# 1_power.net
KiCad netlist of a schematic drawn in Altium Designer
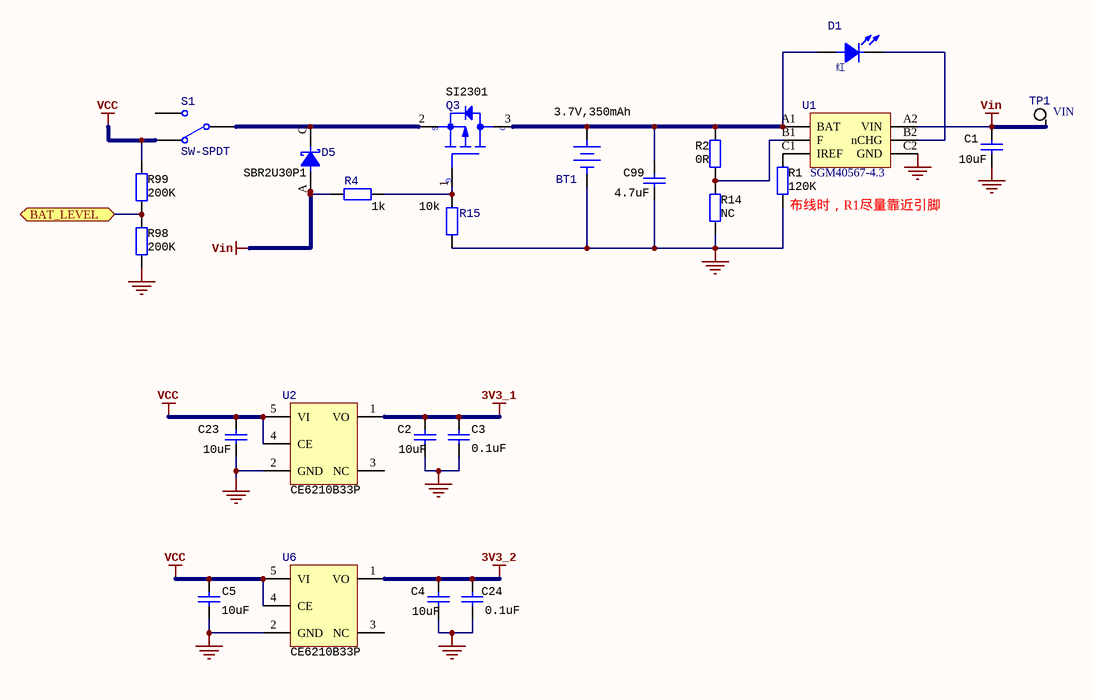
[diagram p0: 1.power.SchDoc]

(export (version "E")
  (design (tool "Eeschema 10.0.6"))
  (components
    (comp (ref "BT1")
      (value "3.7V,350mAh")
      (footprint "2P/1.0MM立式贴片座子")
      (description "4.2V Li-lon")
      (fields (field (name "MANUFACTURER") "?"))
      (libsource (lib "03.常用器件") (part "Battery"))
    )
    (comp (ref "C1")
      (value "10uF")
      (footprint "C0603")
      (description "CAP, CERM, 0.01uF, 100V, +/-5%, X7R, 0603")
      (fields (field (name "PARTNUMBER") "06031C103JAT2A") (field (name "MANUFACTURER") "AVX"))
      (libsource (lib "03.常用器件") (part "CAP1_npol"))
    )
    (comp (ref "C2")
      (value "10uF")
      (footprint "0603")
      (description "CAP, CERM, 0.01uF, 100V, +/-5%, X7R, 0603")
      (fields (field (name "PARTNUMBER") "06031C103JAT2A") (field (name "MANUFACTURER") "AVX"))
      (libsource (lib "03.常用器件") (part "CAP1_npol"))
    )
    (comp (ref "C3")
      (value "0.1uF")
      (footprint "0402")
      (description "CAP, CERM, 0.01uF, 100V, +/-5%, X7R, 0603")
      (fields (field (name "PARTNUMBER") "06031C103JAT2A") (field (name "MANUFACTURER") "AVX"))
      (libsource (lib "03.常用器件") (part "CAP1_npol"))
    )
    (comp (ref "C4")
      (value "10uF")
      (footprint "0603")
      (description "CAP, CERM, 0.01uF, 100V, +/-5%, X7R, 0603")
      (fields (field (name "PARTNUMBER") "06031C103JAT2A") (field (name "MANUFACTURER") "AVX"))
      (libsource (lib "03.常用器件") (part "CAP1_npol"))
    )
    (comp (ref "C5")
      (value "10uF")
      (footprint "0603")
      (description "CAP, CERM, 0.01uF, 100V, +/-5%, X7R, 0603")
      (fields (field (name "PARTNUMBER") "06031C103JAT2A") (field (name "MANUFACTURER") "AVX"))
      (libsource (lib "03.常用器件") (part "CAP1_npol"))
    )
    (comp (ref "C23")
      (value "10uF")
      (footprint "0603")
      (description "CAP, CERM, 0.01uF, 100V, +/-5%, X7R, 0603")
      (fields (field (name "PARTNUMBER") "06031C103JAT2A") (field (name "MANUFACTURER") "AVX"))
      (libsource (lib "03.常用器件") (part "CAP1_npol"))
    )
    (comp (ref "C24")
      (value "0.1uF")
      (footprint "0402")
      (description "CAP, CERM, 0.01uF, 100V, +/-5%, X7R, 0603")
      (fields (field (name "PARTNUMBER") "06031C103JAT2A") (field (name "MANUFACTURER") "AVX"))
      (libsource (lib "03.常用器件") (part "CAP1_npol"))
    )
    (comp (ref "C99")
      (value "4.7uF")
      (footprint "C0603")
      (description "CAP, CERM, 0.01uF, 100V, +/-5%, X7R, 0603")
      (fields (field (name "PARTNUMBER") "06031C103JAT2A") (field (name "MANUFACTURER") "AVX"))
      (libsource (lib "03.常用器件") (part "CAP1_npol"))
    )
    (comp (ref "D1")
      (value "红")
      (footprint "0603LED")
      (fields (field (name "MANUFACTURER") "?"))
      (libsource (lib "03.常用器件") (part "LED1"))
    )
    (comp (ref "D5")
      (value "SBR2U30P1")
      (footprint "POWERDI123")
      (fields (field (name "PARTNUMBER") "?") (field (name "PUBLISHER") "Altium Limited"))
      (libsource (lib "03.常用器件") (part "Diode_Schottky"))
    )
    (comp (ref "Q3")
      (value "SI2301")
      (footprint "SOT23-3")
      (fields (field (name "MANUFACTURER") "?"))
      (libsource (lib "03.常用器件") (part "PMOS"))
    )
    (comp (ref "R1")
      (value "120K")
      (footprint "R0402")
      (description "RES, 1.0k ohm, 5%, 0.1W, 0603")
      (fields
        (field (name "PARTNUMBER") "RC0603JR-071KL")
        (field (name "MANUFACTURER") "Yageo America")
        (field (name "PUBLISHER") "Texas Instruments")
      )
      (libsource (lib "") (part "RES1_1"))
    )
    (comp (ref "R2")
      (value "0R")
      (footprint "R0402")
      (description "RES, 1.0k ohm, 5%, 0.1W, 0603")
      (fields
        (field (name "PARTNUMBER") "RC0603JR-071KL")
        (field (name "MANUFACTURER") "Yageo America")
        (field (name "PUBLISHER") "Texas Instruments")
      )
      (libsource (lib "03.常用器件") (part "RES1"))
    )
    (comp (ref "R4")
      (value "1k")
      (footprint "R0402")
      (description "Resistor")
      (fields (field (name "PUBLISHER") "Altium Limited"))
      (libsource (lib "") (part "Res2_1"))
    )
    (comp (ref "R14")
      (value "NC")
      (footprint "R0402")
      (description "RES, 1.0k ohm, 5%, 0.1W, 0603")
      (fields
        (field (name "PARTNUMBER") "RC0603JR-071KL")
        (field (name "MANUFACTURER") "Yageo America")
        (field (name "PUBLISHER") "Texas Instruments")
      )
      (libsource (lib "03.常用器件") (part "RES1"))
    )
    (comp (ref "R15")
      (value "10k")
      (footprint "R0402")
      (description "Resistor")
      (fields (field (name "PUBLISHER") "Altium Limited"))
      (libsource (lib "Miscellaneous Devices") (part "Res2"))
    )
    (comp (ref "R98")
      (value "200K")
      (footprint "R0402")
      (description "RES, 1.0k ohm, 5%, 0.1W, 0603")
      (fields
        (field (name "PARTNUMBER") "RC0603JR-071KL")
        (field (name "MANUFACTURER") "Yageo America")
        (field (name "PUBLISHER") "Texas Instruments")
      )
      (libsource (lib "") (part "RES1_1"))
    )
    (comp (ref "R99")
      (value "200K")
      (footprint "R0402")
      (description "RES, 1.0k ohm, 5%, 0.1W, 0603")
      (fields
        (field (name "PARTNUMBER") "RC0603JR-071KL")
        (field (name "MANUFACTURER") "Yageo America")
        (field (name "PUBLISHER") "Texas Instruments")
      )
      (libsource (lib "") (part "RES1_1"))
    )
    (comp (ref "S1")
      (value "SW-SPDT")
      (footprint "SW2")
      (description "SPDT Subminiature Toggle Switch, Right Angle Mounting, Vertical Actuation")
      (fields (field (name "PUBLISHER") "Altium Limited"))
      (libsource (lib "Miscellaneous Devices") (part "SW-SPDT"))
    )
    (comp (ref "TP1")
      (value "VIN")
      (footprint "测试点")
      (description "Test Point")
      (libsource (lib "my_Schlib") (part "TP"))
    )
    (comp (ref "U1")
      (value "SGM40567-4.3")
      (footprint "SGM40567")
      (description "充电IC")
      (libsource (lib "SGM40567") (part "SGM40567"))
    )
    (comp (ref "U2")
      (value "CE6210B33P")
      (footprint "SOT89-5")
      (libsource (lib "altium-import") (part "root_0_AP2112K_"))
    )
    (comp (ref "U6")
      (value "CE6210B33P")
      (footprint "SOT89-5")
      (libsource (lib "altium-import") (part "root_0_AP2112K_"))
    )
  )
  (nets
    (net (code "1") (name "/BAT_LEVEL") (class "Default")
      (node (ref "R98") (pin "2") (pinfunction "2_2") (pintype "passive"))
      (node (ref "R99") (pin "1") (pinfunction "1_1") (pintype "passive"))
    )
    (net (code "2") (name "3V3_1") (class "Default")
      (node (ref "C2") (pin "1") (pinfunction "1_1") (pintype "passive"))
      (node (ref "C3") (pin "2") (pinfunction "2_2") (pintype "passive"))
      (node (ref "U2") (pin "1") (pinfunction "VO_1") (pintype "passive"))
    )
    (net (code "3") (name "3V3_2") (class "Default")
      (node (ref "C24") (pin "2") (pinfunction "2_2") (pintype "passive"))
      (node (ref "C4") (pin "1") (pinfunction "1_1") (pintype "passive"))
      (node (ref "U6") (pin "1") (pinfunction "VO_1") (pintype "passive"))
    )
    (net (code "4") (name "<NO NET>") (class "Default")
      (node (ref "BT1") (pin "2") (pinfunction "-_2") (pintype "passive"))
      (node (ref "C1") (pin "2") (pinfunction "2_2") (pintype "passive"))
      (node (ref "C2") (pin "2") (pinfunction "2_2") (pintype "passive"))
      (node (ref "C23") (pin "2") (pinfunction "2_2") (pintype "passive"))
      (node (ref "C24") (pin "1") (pinfunction "1_1") (pintype "passive"))
      (node (ref "C3") (pin "1") (pinfunction "1_1") (pintype "passive"))
      (node (ref "C4") (pin "2") (pinfunction "2_2") (pintype "passive"))
      (node (ref "C5") (pin "2") (pinfunction "2_2") (pintype "passive"))
      (node (ref "C99") (pin "2") (pinfunction "2_2") (pintype "passive"))
      (node (ref "R1") (pin "1") (pinfunction "1_1") (pintype "passive"))
      (node (ref "R14") (pin "2") (pinfunction "2_2") (pintype "passive"))
      (node (ref "R15") (pin "1") (pinfunction "1_1") (pintype "passive"))
      (node (ref "R98") (pin "1") (pinfunction "1_1") (pintype "passive"))
      (node (ref "U1") (pin "C2") (pinfunction "GND_C2") (pintype "passive"))
      (node (ref "U2") (pin "2") (pinfunction "GND_2") (pintype "passive"))
      (node (ref "U6") (pin "2") (pinfunction "GND_2") (pintype "passive"))
    )
    (net (code "5") (name "Net-(BT1-+)") (class "Default")
      (node (ref "BT1") (pin "1") (pinfunction "+_1") (pintype "passive"))
      (node (ref "C99") (pin "1") (pinfunction "1_1") (pintype "passive"))
      (node (ref "D1") (pin "A") (pinfunction "ANODE_A") (pintype "passive"))
      (node (ref "Q3") (pin "3") (pinfunction "DRAIN_3") (pintype "passive"))
      (node (ref "R2") (pin "1") (pinfunction "1_1") (pintype "passive"))
      (node (ref "U1") (pin "A1") (pinfunction "BAT_A1") (pintype "passive"))
    )
    (net (code "6") (name "Net-(D1-CATHODE)") (class "Default")
      (node (ref "D1") (pin "C") (pinfunction "CATHODE_C") (pintype "passive"))
      (node (ref "U1") (pin "B2") (pinfunction "nCHG_B2") (pintype "passive"))
    )
    (net (code "7") (name "Net-(D5-CATHODE)") (class "Default")
      (node (ref "D5") (pin "C") (pinfunction "CATHODE_C") (pintype "passive"))
      (node (ref "Q3") (pin "2") (pinfunction "SOURCE_2") (pintype "passive"))
      (node (ref "S1") (pin "2") (pinfunction "2_2") (pintype "passive"))
    )
    (net (code "8") (name "Net-(Q3-GATE)") (class "Default")
      (node (ref "Q3") (pin "1") (pinfunction "GATE_1") (pintype "passive"))
      (node (ref "R15") (pin "2") (pinfunction "2_2") (pintype "passive"))
      (node (ref "R4") (pin "1") (pinfunction "1_1") (pintype "passive"))
    )
    (net (code "9") (name "Net-(U1-F)") (class "Default")
      (node (ref "R14") (pin "1") (pinfunction "1_1") (pintype "passive"))
      (node (ref "R2") (pin "2") (pinfunction "2_2") (pintype "passive"))
      (node (ref "U1") (pin "B1") (pinfunction "F_B1") (pintype "passive"))
    )
    (net (code "10") (name "Net-(U1-IREF)") (class "Default")
      (node (ref "R1") (pin "2") (pinfunction "2_2") (pintype "passive"))
      (node (ref "U1") (pin "C1") (pinfunction "IREF_C1") (pintype "passive"))
    )
    (net (code "11") (name "VCC") (class "Default")
      (node (ref "C23") (pin "1") (pinfunction "1_1") (pintype "passive"))
      (node (ref "C5") (pin "1") (pinfunction "1_1") (pintype "passive"))
      (node (ref "R99") (pin "2") (pinfunction "2_2") (pintype "passive"))
      (node (ref "S1") (pin "3") (pinfunction "3_3") (pintype "passive"))
      (node (ref "U2") (pin "4") (pinfunction "CE_4") (pintype "passive"))
      (node (ref "U2") (pin "5") (pinfunction "VI_5") (pintype "passive"))
      (node (ref "U6") (pin "4") (pinfunction "CE_4") (pintype "passive"))
      (node (ref "U6") (pin "5") (pinfunction "VI_5") (pintype "passive"))
    )
    (net (code "12") (name "Vin") (class "Default")
      (node (ref "C1") (pin "1") (pinfunction "1_1") (pintype "passive"))
      (node (ref "D5") (pin "A") (pinfunction "ANODE_A") (pintype "passive"))
      (node (ref "R4") (pin "2") (pinfunction "2_2") (pintype "passive"))
      (node (ref "TP1") (pin "1") (pinfunction "1_1") (pintype "passive"))
      (node (ref "U1") (pin "A2") (pinfunction "VIN_A2") (pintype "passive"))
    )
    (net (code "13") (name "unconnected-(S1-Pad1)") (class "Default")
      (node (ref "S1") (pin "1") (pinfunction "1_1") (pintype "passive"))
    )
    (net (code "14") (name "unconnected-(U2-NC-Pad3)") (class "Default")
      (node (ref "U2") (pin "3") (pinfunction "NC_3") (pintype "passive"))
    )
    (net (code "15") (name "unconnected-(U6-NC-Pad3)") (class "Default")
      (node (ref "U6") (pin "3") (pinfunction "NC_3") (pintype "passive"))
    )
  )
)
